# wifilamp2a.net
KiCad netlist of a schematic drawn in EAGLE
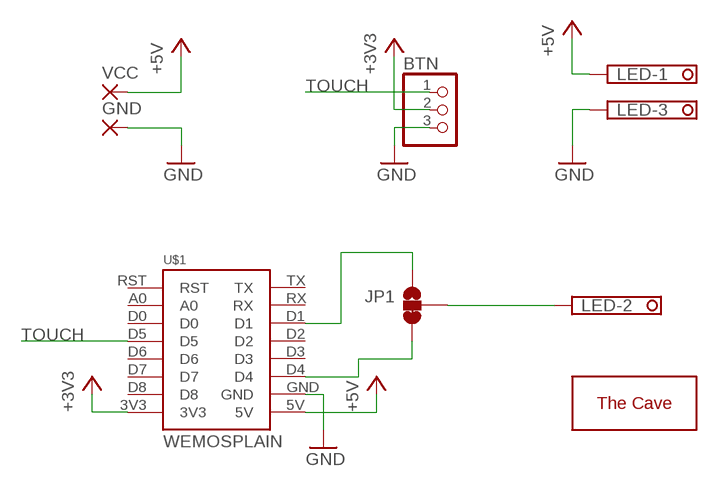
[diagram p0: schematic, sheet 1]

(export (version "E")
  (design (tool "Eeschema 10.0.6"))
  (components
    (comp (ref "BTN")
      (value "PINHD-1X3")
      (footprint "eagle-import:1X03")
      (libsource (lib "eagle-import") (part "PINHD-1X3"))
    )
    (comp (ref "GND")
      (value "WIREPAD3,81/1,4")
      (footprint "eagle-import:3,81_1,4")
      (libsource (lib "eagle-import") (part "WIREPAD3,81/1,4"))
    )
    (comp (ref "JP1")
      (value "JUMPER-SMT_3_1-NC_TRACE_NO-SILK")
      (footprint "eagle-import:SMT-JUMPER_3_1-NC_TRACE_NO-SILK")
      (libsource (lib "eagle-import") (part "JUMPER-SMT_3_1-NC_TRACE_NO-SILK"))
    )
    (comp (ref "LED")
      (value "1751251")
      (footprint "eagle-import:1751251")
      (libsource (lib "eagle-import") (part "1751251"))
    )
    (comp (ref "U$1")
      (value "WEMOSPLAIN")
      (footprint "eagle-import:WEMOS-PLAIN")
      (libsource (lib "eagle-import") (part "WEMOSPLAIN"))
    )
    (comp (ref "U$2")
      (value "THECAVE_LOGO_TOP_SMALL")
      (footprint "eagle-import:LOGO_TOP_SMALL")
      (libsource (lib "eagle-import") (part "THECAVE_LOGO_TOP_SMALL"))
    )
    (comp (ref "VCC")
      (value "PAD3,81/2")
      (footprint "eagle-import:PAD3,81_2")
      (libsource (lib "eagle-import") (part "PAD3,81/2"))
    )
  )
  (nets
    (net (code "1") (name "+3V3") (class "Default")
      (node (ref "BTN") (pin "2") (pinfunction "2_2") (pintype "passive"))
      (node (ref "U$1") (pin "3V3") (pinfunction "3V3_3V3") (pintype "bidirectional"))
    )
    (net (code "2") (name "+5V") (class "Default")
      (node (ref "LED") (pin "1") (pinfunction "K_1") (pintype "passive"))
      (node (ref "U$1") (pin "5V") (pinfunction "5V_5V") (pintype "bidirectional"))
      (node (ref "VCC") (pin "1") (pinfunction "P_1") (pintype "passive"))
    )
    (net (code "3") (name "/TOUCH") (class "Default")
      (node (ref "BTN") (pin "1") (pinfunction "1_1") (pintype "passive"))
      (node (ref "U$1") (pin "D5") (pinfunction "D5_D5") (pintype "bidirectional"))
    )
    (net (code "4") (name "GND") (class "Default")
      (node (ref "BTN") (pin "3") (pinfunction "3_3") (pintype "passive"))
      (node (ref "GND") (pin "1") (pinfunction "P_1") (pintype "passive"))
      (node (ref "LED") (pin "3") (pinfunction "K_3") (pintype "passive"))
      (node (ref "U$1") (pin "GND") (pinfunction "GND_GND") (pintype "bidirectional"))
    )
    (net (code "5") (name "Net-(JP1-Pad1)") (class "Default")
      (node (ref "JP1") (pin "1") (pinfunction "1_1") (pintype "passive"))
      (node (ref "U$1") (pin "D1") (pinfunction "D1_D1") (pintype "bidirectional"))
    )
    (net (code "6") (name "Net-(JP1-Pad3)") (class "Default")
      (node (ref "JP1") (pin "3") (pinfunction "3_3") (pintype "passive"))
      (node (ref "U$1") (pin "D4") (pinfunction "D4_D4") (pintype "bidirectional"))
    )
    (net (code "7") (name "Net-(LEDB-K)") (class "Default")
      (node (ref "JP1") (pin "2") (pinfunction "2_2") (pintype "passive"))
      (node (ref "LED") (pin "2") (pinfunction "K_2") (pintype "passive"))
    )
    (net (code "8") (name "unconnected-(U$1-PadA0)") (class "Default")
      (node (ref "U$1") (pin "A0") (pinfunction "A0_A0") (pintype "bidirectional"))
    )
    (net (code "9") (name "unconnected-(U$1-PadD0)") (class "Default")
      (node (ref "U$1") (pin "D0") (pinfunction "D0_D0") (pintype "bidirectional"))
    )
    (net (code "10") (name "unconnected-(U$1-PadD2)") (class "Default")
      (node (ref "U$1") (pin "D2") (pinfunction "D2_D2") (pintype "bidirectional"))
    )
    (net (code "11") (name "unconnected-(U$1-PadD3)") (class "Default")
      (node (ref "U$1") (pin "D3") (pinfunction "D3_D3") (pintype "bidirectional"))
    )
    (net (code "12") (name "unconnected-(U$1-PadD6)") (class "Default")
      (node (ref "U$1") (pin "D6") (pinfunction "D6_D6") (pintype "bidirectional"))
    )
    (net (code "13") (name "unconnected-(U$1-PadD7)") (class "Default")
      (node (ref "U$1") (pin "D7") (pinfunction "D7_D7") (pintype "bidirectional"))
    )
    (net (code "14") (name "unconnected-(U$1-PadD8)") (class "Default")
      (node (ref "U$1") (pin "D8") (pinfunction "D8_D8") (pintype "bidirectional"))
    )
    (net (code "15") (name "unconnected-(U$1-PadRST)") (class "Default")
      (node (ref "U$1") (pin "RST") (pinfunction "RST_RST") (pintype "bidirectional"))
    )
    (net (code "16") (name "unconnected-(U$1-PadRX)") (class "Default")
      (node (ref "U$1") (pin "RX") (pinfunction "RX_RX") (pintype "bidirectional"))
    )
    (net (code "17") (name "unconnected-(U$1-PadTX)") (class "Default")
      (node (ref "U$1") (pin "TX") (pinfunction "TX_TX") (pintype "bidirectional"))
    )
  )
)
